# LCD_Schem.net
KiCad netlist of a schematic drawn in Altium Designer
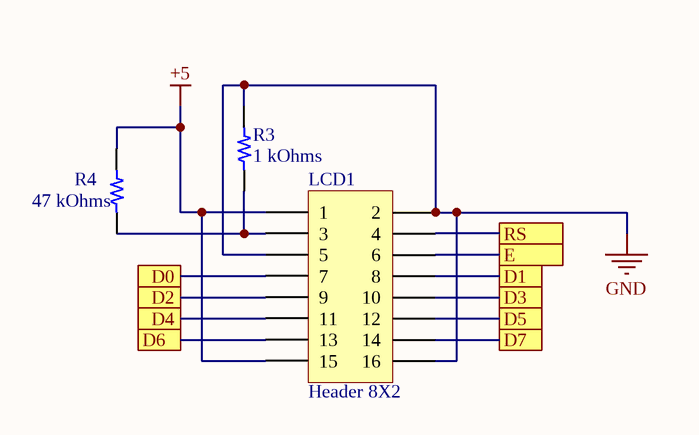
[diagram p0: LCD_Schem.SchDoc]

(export (version "E")
  (design (tool "Eeschema 10.0.6"))
  (components
    (comp (ref "LCD1")
      (value "Header 8X2")
      (footprint "HDR2X8")
      (description "Header, 8-Pin, Dual row")
      (fields (field (name "PUBLISHER") "Altium Limited"))
      (libsource (lib "Miscellaneous Connectors") (part "Header 8X2"))
    )
    (comp (ref "R3")
      (value "1 kOhms")
      (footprint "RES 1210_3225")
      (description "RES SMD 1K OHM 5% 2/3W 1210")
      (fields (field (name "PART NUMBER") "ESR25JZPJ102") (field (name "MANUFACTURER") "Rohm Semiconductor"))
      (libsource (lib "Celestial Altium Library - altium_library") (part "Resistor"))
    )
    (comp (ref "R4")
      (value "47 kOhms")
      (footprint "RES 1210_3225")
      (description "RES 47K OHM 1% 3/4W 1210")
      (fields
        (field (name "PART NUMBER") "CRGP1210F47K")
        (field (name "MANUFACTURER") "TE Connectivity Passive Product")
      )
      (libsource (lib "Celestial Altium Library - altium_library") (part "Resistor"))
    )
  )
  (nets
    (net (code "1") (name "+5") (class "Default")
      (node (ref "LCD1") (pin "1") (pinfunction "1_1") (pintype "passive"))
      (node (ref "LCD1") (pin "15") (pinfunction "15_15") (pintype "passive"))
      (node (ref "R4") (pin "2") (pinfunction "2_2") (pintype "passive"))
    )
    (net (code "2") (name "/D0") (class "Default")
      (node (ref "LCD1") (pin "7") (pinfunction "7_7") (pintype "passive"))
    )
    (net (code "3") (name "/D1") (class "Default")
      (node (ref "LCD1") (pin "8") (pinfunction "8_8") (pintype "passive"))
    )
    (net (code "4") (name "/D2") (class "Default")
      (node (ref "LCD1") (pin "9") (pinfunction "9_9") (pintype "passive"))
    )
    (net (code "5") (name "/D3") (class "Default")
      (node (ref "LCD1") (pin "10") (pinfunction "10_10") (pintype "passive"))
    )
    (net (code "6") (name "/D4") (class "Default")
      (node (ref "LCD1") (pin "11") (pinfunction "11_11") (pintype "passive"))
    )
    (net (code "7") (name "/D5") (class "Default")
      (node (ref "LCD1") (pin "12") (pinfunction "12_12") (pintype "passive"))
    )
    (net (code "8") (name "/D6") (class "Default")
      (node (ref "LCD1") (pin "13") (pinfunction "13_13") (pintype "passive"))
    )
    (net (code "9") (name "/D7") (class "Default")
      (node (ref "LCD1") (pin "14") (pinfunction "14_14") (pintype "passive"))
    )
    (net (code "10") (name "/E") (class "Default")
      (node (ref "LCD1") (pin "6") (pinfunction "6_6") (pintype "passive"))
    )
    (net (code "11") (name "/RS") (class "Default")
      (node (ref "LCD1") (pin "4") (pinfunction "4_4") (pintype "passive"))
    )
    (net (code "12") (name "GND") (class "Default")
      (node (ref "LCD1") (pin "16") (pinfunction "16_16") (pintype "passive"))
      (node (ref "LCD1") (pin "2") (pinfunction "2_2") (pintype "passive"))
      (node (ref "LCD1") (pin "5") (pinfunction "5_5") (pintype "passive"))
      (node (ref "R3") (pin "2") (pinfunction "2_2") (pintype "passive"))
    )
    (net (code "13") (name "Net-(LCD1-Pad3)") (class "Default")
      (node (ref "LCD1") (pin "3") (pinfunction "3_3") (pintype "passive"))
      (node (ref "R3") (pin "1") (pinfunction "1_1") (pintype "passive"))
      (node (ref "R4") (pin "1") (pinfunction "1_1") (pintype "passive"))
    )
  )
)
